# ledsor.net
KiCad netlist of a schematic drawn in EAGLE
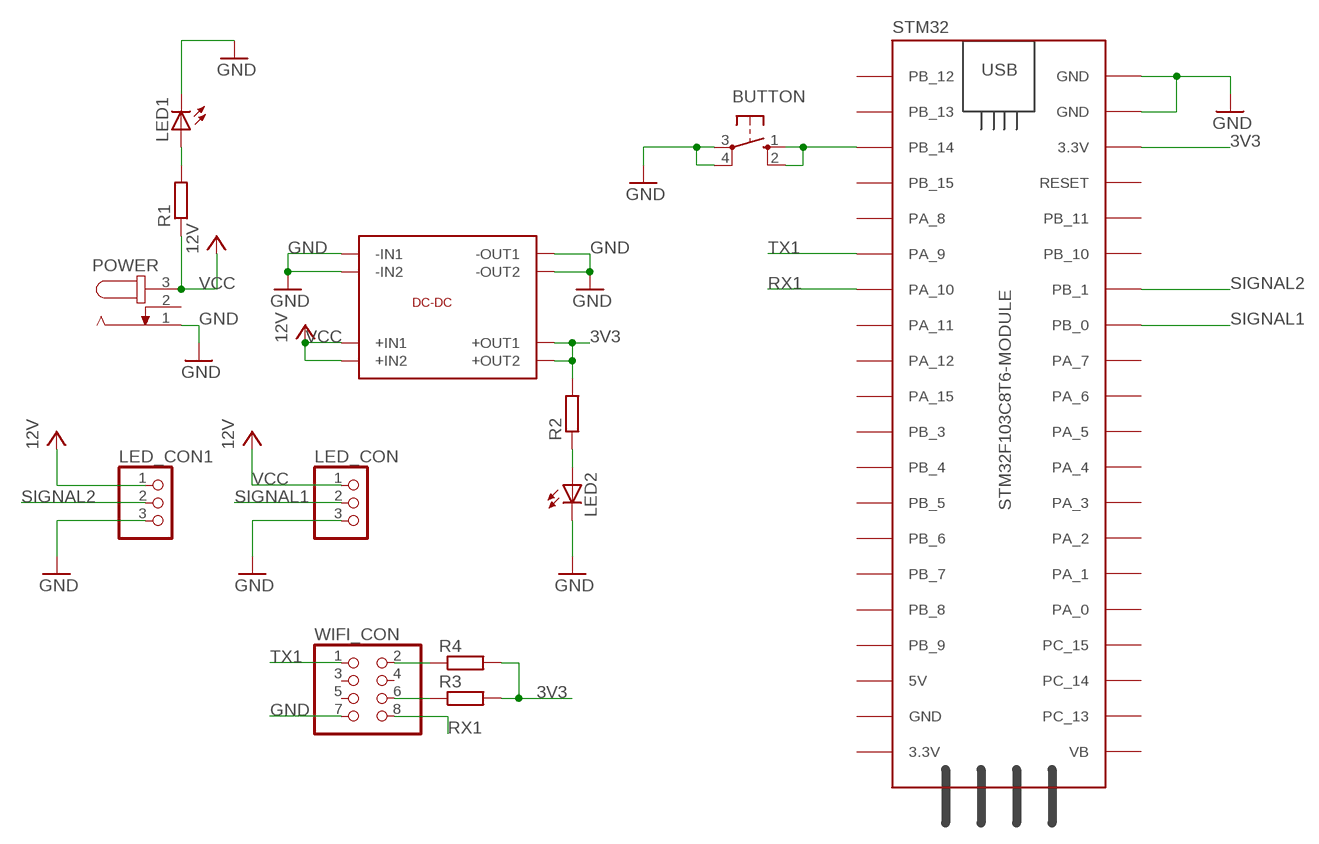
[diagram p0: schematic, sheet 1]

(export (version "E")
  (design (tool "Eeschema 10.0.6"))
  (components
    (comp (ref "BUTTON")
      (value "10-XX")
      (footprint "eagle-import:B3F-10XX")
      (fields (field (name "MPN") "B3F-1000"))
      (libsource (lib "eagle-import") (part "10-XX"))
    )
    (comp (ref "DC-DC")
      (value "SDVR_SMALL")
      (footprint "eagle-import:SDVR_SMALL")
      (libsource (lib "eagle-import") (part "SDVR_SMALL"))
    )
    (comp (ref "LED1")
      (value "LED5MM")
      (footprint "eagle-import:LED5MM")
      (libsource (lib "eagle-import") (part "LED5MM"))
    )
    (comp (ref "LED2")
      (value "LED5MM")
      (footprint "eagle-import:LED5MM")
      (libsource (lib "eagle-import") (part "LED5MM"))
    )
    (comp (ref "LED_CON")
      (value "PINHD-1X3")
      (footprint "eagle-import:1X03")
      (libsource (lib "eagle-import") (part "PINHD-1X3"))
    )
    (comp (ref "LED_CON1")
      (value "PINHD-1X3")
      (footprint "eagle-import:1X03")
      (libsource (lib "eagle-import") (part "PINHD-1X3"))
    )
    (comp (ref "POWER")
      (value "JACK-PLUG1")
      (footprint "eagle-import:SPC4078")
      (libsource (lib "eagle-import") (part "JACK-PLUG1"))
    )
    (comp (ref "R1")
      (value "R-EU_0204/7")
      (footprint "eagle-import:0204_7")
      (libsource (lib "eagle-import") (part "R-EU_0204/7"))
    )
    (comp (ref "R2")
      (value "R-EU_0204/7")
      (footprint "eagle-import:0204_7")
      (libsource (lib "eagle-import") (part "R-EU_0204/7"))
    )
    (comp (ref "R3")
      (value "R-EU_0204/7")
      (footprint "eagle-import:0204_7")
      (libsource (lib "eagle-import") (part "R-EU_0204/7"))
    )
    (comp (ref "R4")
      (value "R-EU_0204/7")
      (footprint "eagle-import:0204_7")
      (libsource (lib "eagle-import") (part "R-EU_0204/7"))
    )
    (comp (ref "STM32")
      (value "STM32F103C8T6-MODULE")
      (footprint "eagle-import:STM32F103C8T6-MODULE")
      (libsource (lib "eagle-import") (part "STM32F103C8T6-MODULE"))
    )
    (comp (ref "WIFI_CON")
      (value "PINHD-2X4")
      (footprint "eagle-import:2X04")
      (libsource (lib "eagle-import") (part "PINHD-2X4"))
    )
  )
  (nets
    (net (code "1") (name "/3V3") (class "Default")
      (node (ref "DC-DC") (pin "P$7") (pinfunction "+OUT1_P$7") (pintype "bidirectional"))
      (node (ref "DC-DC") (pin "P$8") (pinfunction "+OUT2_P$8") (pintype "bidirectional"))
      (node (ref "R2") (pin "2") (pinfunction "2_2") (pintype "passive"))
      (node (ref "R3") (pin "2") (pinfunction "2_2") (pintype "passive"))
      (node (ref "R4") (pin "2") (pinfunction "2_2") (pintype "passive"))
      (node (ref "STM32") (pin "3.3V_2") (pinfunction "3.3V_3.3V_2") (pintype "bidirectional"))
    )
    (net (code "2") (name "/RX1") (class "Default")
      (node (ref "STM32") (pin "PA_10") (pinfunction "PA_10_PA_10") (pintype "bidirectional"))
      (node (ref "WIFI_CON") (pin "8") (pinfunction "8_8") (pintype "passive"))
    )
    (net (code "3") (name "/SIGNAL1") (class "Default")
      (node (ref "LED_CON") (pin "2") (pinfunction "2_2") (pintype "passive"))
      (node (ref "STM32") (pin "PB_0") (pinfunction "PB_0_PB_0") (pintype "bidirectional"))
    )
    (net (code "4") (name "/SIGNAL2") (class "Default")
      (node (ref "LED_CON1") (pin "2") (pinfunction "2_2") (pintype "passive"))
      (node (ref "STM32") (pin "PB_1") (pinfunction "PB_1_PB_1") (pintype "bidirectional"))
    )
    (net (code "5") (name "/TX1") (class "Default")
      (node (ref "STM32") (pin "PA_9") (pinfunction "PA_9_PA_9") (pintype "bidirectional"))
      (node (ref "WIFI_CON") (pin "1") (pinfunction "1_1") (pintype "passive"))
    )
    (net (code "6") (name "12V") (class "Default")
      (node (ref "DC-DC") (pin "P$3") (pinfunction "+IN1_P$3") (pintype "bidirectional"))
      (node (ref "DC-DC") (pin "P$4") (pinfunction "+IN2_P$4") (pintype "bidirectional"))
      (node (ref "LED_CON") (pin "1") (pinfunction "1_1") (pintype "passive"))
      (node (ref "LED_CON1") (pin "1") (pinfunction "1_1") (pintype "passive"))
      (node (ref "POWER") (pin "3") (pinfunction "3_3") (pintype "passive"))
      (node (ref "R1") (pin "1") (pinfunction "1_1") (pintype "passive"))
    )
    (net (code "7") (name "GND") (class "Default")
      (node (ref "BUTTON") (pin "3") (pinfunction "P_3") (pintype "passive"))
      (node (ref "BUTTON") (pin "4") (pinfunction "P1_4") (pintype "passive"))
      (node (ref "DC-DC") (pin "P$1") (pinfunction "-IN1_P$1") (pintype "bidirectional"))
      (node (ref "DC-DC") (pin "P$2") (pinfunction "-IN2_P$2") (pintype "bidirectional"))
      (node (ref "DC-DC") (pin "P$5") (pinfunction "-OUT1_P$5") (pintype "bidirectional"))
      (node (ref "DC-DC") (pin "P$6") (pinfunction "-OUT2_P$6") (pintype "bidirectional"))
      (node (ref "LED1") (pin "K") (pinfunction "C_K") (pintype "passive"))
      (node (ref "LED2") (pin "K") (pinfunction "C_K") (pintype "passive"))
      (node (ref "LED_CON") (pin "3") (pinfunction "3_3") (pintype "passive"))
      (node (ref "LED_CON1") (pin "3") (pinfunction "3_3") (pintype "passive"))
      (node (ref "POWER") (pin "1") (pinfunction "1_1") (pintype "passive"))
      (node (ref "STM32") (pin "GND_2") (pinfunction "GND_GND_2") (pintype "bidirectional"))
      (node (ref "STM32") (pin "GND_3") (pinfunction "GND_GND_3") (pintype "power_in"))
      (node (ref "WIFI_CON") (pin "7") (pinfunction "7_7") (pintype "passive"))
    )
    (net (code "8") (name "Net-(BUTTON-S)") (class "Default")
      (node (ref "BUTTON") (pin "1") (pinfunction "S_1") (pintype "passive"))
      (node (ref "BUTTON") (pin "2") (pinfunction "S1_2") (pintype "passive"))
      (node (ref "STM32") (pin "PB_14") (pinfunction "PB_14_PB_14") (pintype "bidirectional"))
    )
    (net (code "9") (name "Net-(LED1-PadA)") (class "Default")
      (node (ref "LED1") (pin "A") (pinfunction "A_A") (pintype "passive"))
      (node (ref "R1") (pin "2") (pinfunction "2_2") (pintype "passive"))
    )
    (net (code "10") (name "Net-(LED2-PadA)") (class "Default")
      (node (ref "LED2") (pin "A") (pinfunction "A_A") (pintype "passive"))
      (node (ref "R2") (pin "1") (pinfunction "1_1") (pintype "passive"))
    )
    (net (code "11") (name "Net-(R3-Pad1)") (class "Default")
      (node (ref "R3") (pin "1") (pinfunction "1_1") (pintype "passive"))
      (node (ref "WIFI_CON") (pin "6") (pinfunction "6_6") (pintype "passive"))
    )
    (net (code "12") (name "Net-(R4-Pad1)") (class "Default")
      (node (ref "R4") (pin "1") (pinfunction "1_1") (pintype "passive"))
      (node (ref "WIFI_CON") (pin "2") (pinfunction "2_2") (pintype "passive"))
    )
    (net (code "13") (name "unconnected-(POWER-Pad2)") (class "Default")
      (node (ref "POWER") (pin "2") (pinfunction "2_2") (pintype "passive"))
    )
    (net (code "14") (name "unconnected-(STM32-3.3V-Pad3.3V_1)") (class "Default")
      (node (ref "STM32") (pin "3.3V_1") (pinfunction "3.3V_3.3V_1") (pintype "bidirectional"))
    )
    (net (code "15") (name "unconnected-(STM32-GND-PadGND_1)") (class "Default")
      (node (ref "STM32") (pin "GND_1") (pinfunction "GND_GND_1") (pintype "bidirectional"))
    )
    (net (code "16") (name "unconnected-(STM32-Pad5V)") (class "Default")
      (node (ref "STM32") (pin "5V") (pinfunction "5V_5V") (pintype "bidirectional"))
    )
    (net (code "17") (name "unconnected-(STM32-PadPA_0)") (class "Default")
      (node (ref "STM32") (pin "PA_0") (pinfunction "PA_0_PA_0") (pintype "bidirectional"))
    )
    (net (code "18") (name "unconnected-(STM32-PadPA_1)") (class "Default")
      (node (ref "STM32") (pin "PA_1") (pinfunction "PA_1_PA_1") (pintype "bidirectional"))
    )
    (net (code "19") (name "unconnected-(STM32-PadPA_2)") (class "Default")
      (node (ref "STM32") (pin "PA_2") (pinfunction "PA_2_PA_2") (pintype "bidirectional"))
    )
    (net (code "20") (name "unconnected-(STM32-PadPA_3)") (class "Default")
      (node (ref "STM32") (pin "PA_3") (pinfunction "PA_3_PA_3") (pintype "bidirectional"))
    )
    (net (code "21") (name "unconnected-(STM32-PadPA_4)") (class "Default")
      (node (ref "STM32") (pin "PA_4") (pinfunction "PA_4_PA_4") (pintype "bidirectional"))
    )
    (net (code "22") (name "unconnected-(STM32-PadPA_5)") (class "Default")
      (node (ref "STM32") (pin "PA_5") (pinfunction "PA_5_PA_5") (pintype "bidirectional"))
    )
    (net (code "23") (name "unconnected-(STM32-PadPA_6)") (class "Default")
      (node (ref "STM32") (pin "PA_6") (pinfunction "PA_6_PA_6") (pintype "bidirectional"))
    )
    (net (code "24") (name "unconnected-(STM32-PadPA_7)") (class "Default")
      (node (ref "STM32") (pin "PA_7") (pinfunction "PA_7_PA_7") (pintype "bidirectional"))
    )
    (net (code "25") (name "unconnected-(STM32-PadPA_8)") (class "Default")
      (node (ref "STM32") (pin "PA_8") (pinfunction "PA_8_PA_8") (pintype "bidirectional"))
    )
    (net (code "26") (name "unconnected-(STM32-PadPA_11)") (class "Default")
      (node (ref "STM32") (pin "PA_11") (pinfunction "PA_11_PA_11") (pintype "bidirectional"))
    )
    (net (code "27") (name "unconnected-(STM32-PadPA_12)") (class "Default")
      (node (ref "STM32") (pin "PA_12") (pinfunction "PA_12_PA_12") (pintype "bidirectional"))
    )
    (net (code "28") (name "unconnected-(STM32-PadPA_15)") (class "Default")
      (node (ref "STM32") (pin "PA_15") (pinfunction "PA_15_PA_15") (pintype "bidirectional"))
    )
    (net (code "29") (name "unconnected-(STM32-PadPB_3)") (class "Default")
      (node (ref "STM32") (pin "PB_3") (pinfunction "PB_3_PB_3") (pintype "bidirectional"))
    )
    (net (code "30") (name "unconnected-(STM32-PadPB_4)") (class "Default")
      (node (ref "STM32") (pin "PB_4") (pinfunction "PB_4_PB_4") (pintype "bidirectional"))
    )
    (net (code "31") (name "unconnected-(STM32-PadPB_5)") (class "Default")
      (node (ref "STM32") (pin "PB_5") (pinfunction "PB_5_PB_5") (pintype "bidirectional"))
    )
    (net (code "32") (name "unconnected-(STM32-PadPB_6)") (class "Default")
      (node (ref "STM32") (pin "PB_6") (pinfunction "PB_6_PB_6") (pintype "bidirectional"))
    )
    (net (code "33") (name "unconnected-(STM32-PadPB_7)") (class "Default")
      (node (ref "STM32") (pin "PB_7") (pinfunction "PB_7_PB_7") (pintype "bidirectional"))
    )
    (net (code "34") (name "unconnected-(STM32-PadPB_8)") (class "Default")
      (node (ref "STM32") (pin "PB_8") (pinfunction "PB_8_PB_8") (pintype "bidirectional"))
    )
    (net (code "35") (name "unconnected-(STM32-PadPB_9)") (class "Default")
      (node (ref "STM32") (pin "PB_9") (pinfunction "PB_9_PB_9") (pintype "bidirectional"))
    )
    (net (code "36") (name "unconnected-(STM32-PadPB_10)") (class "Default")
      (node (ref "STM32") (pin "PB_10") (pinfunction "PB_10_PB_10") (pintype "bidirectional"))
    )
    (net (code "37") (name "unconnected-(STM32-PadPB_11)") (class "Default")
      (node (ref "STM32") (pin "PB_11") (pinfunction "PB_11_PB_11") (pintype "bidirectional"))
    )
    (net (code "38") (name "unconnected-(STM32-PadPB_12)") (class "Default")
      (node (ref "STM32") (pin "PB_12") (pinfunction "PB_12_PB_12") (pintype "bidirectional"))
    )
    (net (code "39") (name "unconnected-(STM32-PadPB_13)") (class "Default")
      (node (ref "STM32") (pin "PB_13") (pinfunction "PB_13_PB_13") (pintype "bidirectional"))
    )
    (net (code "40") (name "unconnected-(STM32-PadPB_15)") (class "Default")
      (node (ref "STM32") (pin "PB_15") (pinfunction "PB_15_PB_15") (pintype "bidirectional"))
    )
    (net (code "41") (name "unconnected-(STM32-PadPC_13)") (class "Default")
      (node (ref "STM32") (pin "PC_13") (pinfunction "PC_13_PC_13") (pintype "bidirectional"))
    )
    (net (code "42") (name "unconnected-(STM32-PadPC_14)") (class "Default")
      (node (ref "STM32") (pin "PC_14") (pinfunction "PC_14_PC_14") (pintype "bidirectional"))
    )
    (net (code "43") (name "unconnected-(STM32-PadPC_15)") (class "Default")
      (node (ref "STM32") (pin "PC_15") (pinfunction "PC_15_PC_15") (pintype "bidirectional"))
    )
    (net (code "44") (name "unconnected-(STM32-PadRESET)") (class "Default")
      (node (ref "STM32") (pin "RESET") (pinfunction "RESET_RESET") (pintype "bidirectional"))
    )
    (net (code "45") (name "unconnected-(STM32-PadVB)") (class "Default")
      (node (ref "STM32") (pin "VB") (pinfunction "VB_VB") (pintype "bidirectional"))
    )
    (net (code "46") (name "unconnected-(WIFI_CON-Pad3)") (class "Default")
      (node (ref "WIFI_CON") (pin "3") (pinfunction "3_3") (pintype "passive"))
    )
    (net (code "47") (name "unconnected-(WIFI_CON-Pad4)") (class "Default")
      (node (ref "WIFI_CON") (pin "4") (pinfunction "4_4") (pintype "passive"))
    )
    (net (code "48") (name "unconnected-(WIFI_CON-Pad5)") (class "Default")
      (node (ref "WIFI_CON") (pin "5") (pinfunction "5_5") (pintype "passive"))
    )
  )
)
